# Sheet07.net
KiCad netlist of a schematic drawn in Altium Designer
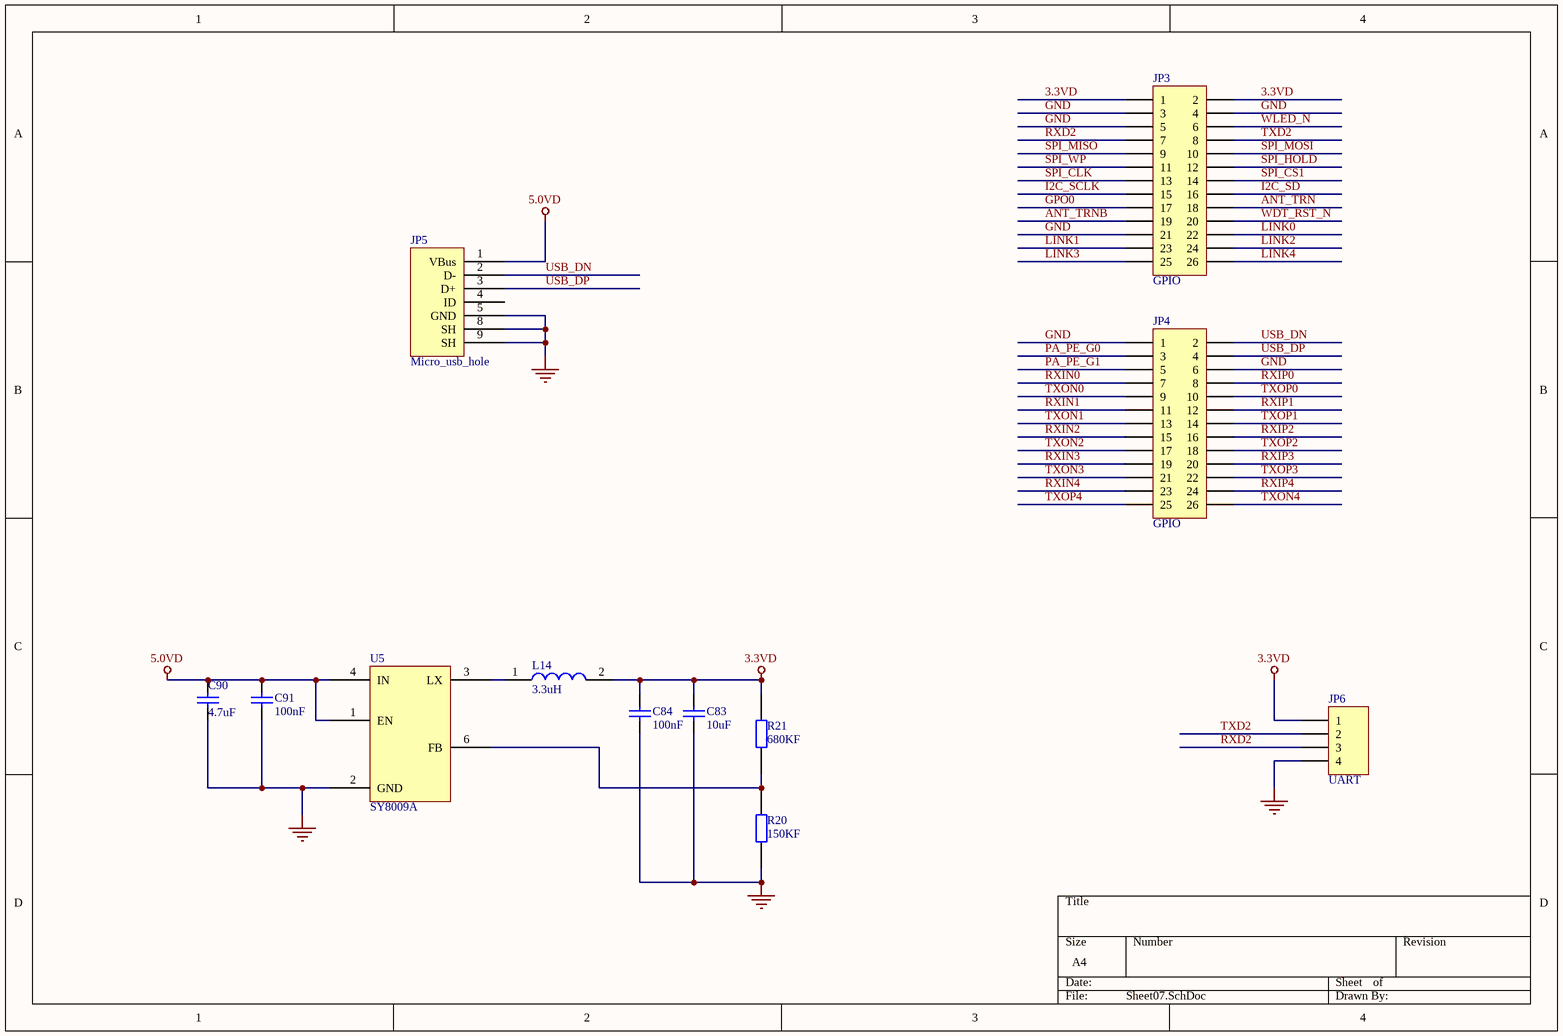
[diagram p0: Sheet07.SchDoc]

(export (version "E")
  (design (tool "Eeschema 10.0.6"))
  (components
    (comp (ref "C83")
      (value "10uF")
      (footprint "R0805")
      (description "2pF, 50V, +/-0.25pF")
      (fields
        (field (name "MANUFACTURER") "Generic Components")
        (field (name "PUBLISHER") "Altium Hobart Technology Centre")
      )
      (libsource (lib "myschlib") (part "Cap Semi"))
    )
    (comp (ref "C84")
      (value "100nF")
      (footprint "R0402")
      (description "2pF, 50V, +/-0.25pF")
      (fields
        (field (name "MANUFACTURER") "Generic Components")
        (field (name "PUBLISHER") "Altium Hobart Technology Centre")
      )
      (libsource (lib "myschlib") (part "Cap Semi"))
    )
    (comp (ref "C90")
      (value "4.7uF")
      (footprint "R0603")
      (description "2pF, 50V, +/-0.25pF")
      (fields
        (field (name "MANUFACTURER") "Generic Components")
        (field (name "PUBLISHER") "Altium Hobart Technology Centre")
      )
      (libsource (lib "myschlib") (part "Cap Semi"))
    )
    (comp (ref "C91")
      (value "100nF")
      (footprint "R0402")
      (description "2pF, 50V, +/-0.25pF")
      (fields
        (field (name "MANUFACTURER") "Generic Components")
        (field (name "PUBLISHER") "Altium Hobart Technology Centre")
      )
      (libsource (lib "myschlib") (part "Cap Semi"))
    )
    (comp (ref "JP3")
      (value "GPIO")
      (footprint "HDR2X13")
      (description "Header, 13-Pin, Dual row")
      (fields (field (name "PUBLISHER") "Altium Limited"))
      (libsource (lib "Miscellaneous Connectors") (part "Header 13X2"))
    )
    (comp (ref "JP4")
      (value "GPIO")
      (footprint "HDR2X13")
      (description "Header, 13-Pin, Dual row")
      (fields (field (name "PUBLISHER") "Altium Limited"))
      (libsource (lib "Miscellaneous Connectors") (part "Header 13X2"))
    )
    (comp (ref "JP5")
      (value "Micro_usb_hole")
      (footprint "Miro_usb_hole")
      (libsource (lib "myschlib") (part "micri_usb_hole"))
    )
    (comp (ref "JP6")
      (value "UART")
      (footprint "HDR1X4")
      (description "Header, 4-Pin")
      (fields (field (name "PUBLISHER") "Altium Limited"))
      (libsource (lib "Miscellaneous Connectors") (part "Header 4"))
    )
    (comp (ref "L14")
      (value "3.3uH")
      (footprint "LSMD3_8x3_8")
      (libsource (lib "myschlib") (part "INDUCTOR"))
    )
    (comp (ref "R20") (value "150KF") (footprint "R0402") (libsource (lib "myschlib") (part "RES")))
    (comp (ref "R21") (value "680KF") (footprint "R0402") (libsource (lib "myschlib") (part "RES")))
    (comp (ref "U5") (value "SY8009A") (footprint "SOT23-6L") (libsource (lib "myschlib") (part "SY8008C")))
  )
  (nets
    (net (code "1") (name "/ANT_TRN") (class "Default")
      (node (ref "JP3") (pin "18") (pinfunction "18_18") (pintype "passive"))
    )
    (net (code "2") (name "/ANT_TRNB") (class "Default")
      (node (ref "JP3") (pin "19") (pinfunction "19_19") (pintype "passive"))
    )
    (net (code "3") (name "/GPO0") (class "Default")
      (node (ref "JP3") (pin "17") (pinfunction "17_17") (pintype "passive"))
    )
    (net (code "4") (name "/I2C_SCLK") (class "Default")
      (node (ref "JP3") (pin "15") (pinfunction "15_15") (pintype "passive"))
    )
    (net (code "5") (name "/I2C_SD") (class "Default")
      (node (ref "JP3") (pin "16") (pinfunction "16_16") (pintype "passive"))
    )
    (net (code "6") (name "/LINK0") (class "Default")
      (node (ref "JP3") (pin "22") (pinfunction "22_22") (pintype "passive"))
    )
    (net (code "7") (name "/LINK1") (class "Default")
      (node (ref "JP3") (pin "23") (pinfunction "23_23") (pintype "passive"))
    )
    (net (code "8") (name "/LINK2") (class "Default")
      (node (ref "JP3") (pin "24") (pinfunction "24_24") (pintype "passive"))
    )
    (net (code "9") (name "/LINK3") (class "Default")
      (node (ref "JP3") (pin "25") (pinfunction "25_25") (pintype "passive"))
    )
    (net (code "10") (name "/LINK4") (class "Default")
      (node (ref "JP3") (pin "26") (pinfunction "26_26") (pintype "passive"))
    )
    (net (code "11") (name "/PA_PE_G0") (class "Default")
      (node (ref "JP4") (pin "3") (pinfunction "3_3") (pintype "passive"))
    )
    (net (code "12") (name "/PA_PE_G1") (class "Default")
      (node (ref "JP4") (pin "5") (pinfunction "5_5") (pintype "passive"))
    )
    (net (code "13") (name "/RXD2") (class "Default")
      (node (ref "JP3") (pin "7") (pinfunction "7_7") (pintype "passive"))
      (node (ref "JP6") (pin "3") (pinfunction "3_3") (pintype "passive"))
    )
    (net (code "14") (name "/RXIN0") (class "Default")
      (node (ref "JP4") (pin "7") (pinfunction "7_7") (pintype "passive"))
    )
    (net (code "15") (name "/RXIN1") (class "Default")
      (node (ref "JP4") (pin "11") (pinfunction "11_11") (pintype "passive"))
    )
    (net (code "16") (name "/RXIN2") (class "Default")
      (node (ref "JP4") (pin "15") (pinfunction "15_15") (pintype "passive"))
    )
    (net (code "17") (name "/RXIN3") (class "Default")
      (node (ref "JP4") (pin "19") (pinfunction "19_19") (pintype "passive"))
    )
    (net (code "18") (name "/RXIN4") (class "Default")
      (node (ref "JP4") (pin "23") (pinfunction "23_23") (pintype "passive"))
    )
    (net (code "19") (name "/RXIP0") (class "Default")
      (node (ref "JP4") (pin "8") (pinfunction "8_8") (pintype "passive"))
    )
    (net (code "20") (name "/RXIP1") (class "Default")
      (node (ref "JP4") (pin "12") (pinfunction "12_12") (pintype "passive"))
    )
    (net (code "21") (name "/RXIP2") (class "Default")
      (node (ref "JP4") (pin "16") (pinfunction "16_16") (pintype "passive"))
    )
    (net (code "22") (name "/RXIP3") (class "Default")
      (node (ref "JP4") (pin "20") (pinfunction "20_20") (pintype "passive"))
    )
    (net (code "23") (name "/RXIP4") (class "Default")
      (node (ref "JP4") (pin "24") (pinfunction "24_24") (pintype "passive"))
    )
    (net (code "24") (name "/SPI_CLK") (class "Default")
      (node (ref "JP3") (pin "13") (pinfunction "13_13") (pintype "passive"))
    )
    (net (code "25") (name "/SPI_CS1") (class "Default")
      (node (ref "JP3") (pin "14") (pinfunction "14_14") (pintype "passive"))
    )
    (net (code "26") (name "/SPI_HOLD") (class "Default")
      (node (ref "JP3") (pin "12") (pinfunction "12_12") (pintype "passive"))
    )
    (net (code "27") (name "/SPI_MISO") (class "Default")
      (node (ref "JP3") (pin "9") (pinfunction "9_9") (pintype "passive"))
    )
    (net (code "28") (name "/SPI_MOSI") (class "Default")
      (node (ref "JP3") (pin "10") (pinfunction "10_10") (pintype "passive"))
    )
    (net (code "29") (name "/SPI_WP") (class "Default")
      (node (ref "JP3") (pin "11") (pinfunction "11_11") (pintype "passive"))
    )
    (net (code "30") (name "/TXD2") (class "Default")
      (node (ref "JP3") (pin "8") (pinfunction "8_8") (pintype "passive"))
      (node (ref "JP6") (pin "2") (pinfunction "2_2") (pintype "passive"))
    )
    (net (code "31") (name "/TXON0") (class "Default")
      (node (ref "JP4") (pin "9") (pinfunction "9_9") (pintype "passive"))
    )
    (net (code "32") (name "/TXON1") (class "Default")
      (node (ref "JP4") (pin "13") (pinfunction "13_13") (pintype "passive"))
    )
    (net (code "33") (name "/TXON2") (class "Default")
      (node (ref "JP4") (pin "17") (pinfunction "17_17") (pintype "passive"))
    )
    (net (code "34") (name "/TXON3") (class "Default")
      (node (ref "JP4") (pin "21") (pinfunction "21_21") (pintype "passive"))
    )
    (net (code "35") (name "/TXON4") (class "Default")
      (node (ref "JP4") (pin "26") (pinfunction "26_26") (pintype "passive"))
    )
    (net (code "36") (name "/TXOP0") (class "Default")
      (node (ref "JP4") (pin "10") (pinfunction "10_10") (pintype "passive"))
    )
    (net (code "37") (name "/TXOP1") (class "Default")
      (node (ref "JP4") (pin "14") (pinfunction "14_14") (pintype "passive"))
    )
    (net (code "38") (name "/TXOP2") (class "Default")
      (node (ref "JP4") (pin "18") (pinfunction "18_18") (pintype "passive"))
    )
    (net (code "39") (name "/TXOP3") (class "Default")
      (node (ref "JP4") (pin "22") (pinfunction "22_22") (pintype "passive"))
    )
    (net (code "40") (name "/TXOP4") (class "Default")
      (node (ref "JP4") (pin "25") (pinfunction "25_25") (pintype "passive"))
    )
    (net (code "41") (name "/USB_DN") (class "Default")
      (node (ref "JP4") (pin "2") (pinfunction "2_2") (pintype "passive"))
      (node (ref "JP5") (pin "2") (pinfunction "D-_2") (pintype "passive"))
    )
    (net (code "42") (name "/USB_DP") (class "Default")
      (node (ref "JP4") (pin "4") (pinfunction "4_4") (pintype "passive"))
      (node (ref "JP5") (pin "3") (pinfunction "D+_3") (pintype "passive"))
    )
    (net (code "43") (name "/WDT_RST_N") (class "Default")
      (node (ref "JP3") (pin "20") (pinfunction "20_20") (pintype "passive"))
    )
    (net (code "44") (name "/WLED_N") (class "Default")
      (node (ref "JP3") (pin "6") (pinfunction "6_6") (pintype "passive"))
    )
    (net (code "45") (name "3.3VD") (class "Default")
      (node (ref "C83") (pin "1") (pinfunction "1_1") (pintype "passive"))
      (node (ref "C84") (pin "1") (pinfunction "1_1") (pintype "passive"))
      (node (ref "JP3") (pin "1") (pinfunction "1_1") (pintype "passive"))
      (node (ref "JP3") (pin "2") (pinfunction "2_2") (pintype "passive"))
      (node (ref "JP6") (pin "1") (pinfunction "1_1") (pintype "passive"))
      (node (ref "L14") (pin "2") (pinfunction "2_2") (pintype "passive"))
      (node (ref "R21") (pin "1") (pinfunction "1_1") (pintype "passive"))
    )
    (net (code "46") (name "5.0VD") (class "Default")
      (node (ref "C90") (pin "2") (pinfunction "2_2") (pintype "passive"))
      (node (ref "C91") (pin "1") (pinfunction "1_1") (pintype "passive"))
      (node (ref "JP5") (pin "1") (pinfunction "VBus_1") (pintype "power_in"))
      (node (ref "U5") (pin "1") (pinfunction "EN_1") (pintype "passive"))
      (node (ref "U5") (pin "4") (pinfunction "IN_4") (pintype "passive"))
    )
    (net (code "47") (name "GND") (class "Default")
      (node (ref "C83") (pin "2") (pinfunction "2_2") (pintype "passive"))
      (node (ref "C84") (pin "2") (pinfunction "2_2") (pintype "passive"))
      (node (ref "C90") (pin "1") (pinfunction "1_1") (pintype "passive"))
      (node (ref "C91") (pin "2") (pinfunction "2_2") (pintype "passive"))
      (node (ref "JP3") (pin "21") (pinfunction "21_21") (pintype "passive"))
      (node (ref "JP3") (pin "3") (pinfunction "3_3") (pintype "passive"))
      (node (ref "JP3") (pin "4") (pinfunction "4_4") (pintype "passive"))
      (node (ref "JP3") (pin "5") (pinfunction "5_5") (pintype "passive"))
      (node (ref "JP4") (pin "1") (pinfunction "1_1") (pintype "passive"))
      (node (ref "JP4") (pin "6") (pinfunction "6_6") (pintype "passive"))
      (node (ref "JP5") (pin "5") (pinfunction "GND_5") (pintype "passive"))
      (node (ref "JP5") (pin "8") (pinfunction "SH_8") (pintype "passive"))
      (node (ref "JP5") (pin "9") (pinfunction "SH_9") (pintype "passive"))
      (node (ref "JP6") (pin "4") (pinfunction "4_4") (pintype "passive"))
      (node (ref "R20") (pin "2") (pinfunction "2_2") (pintype "passive"))
      (node (ref "U5") (pin "2") (pinfunction "GND_2") (pintype "passive"))
    )
    (net (code "48") (name "Net-(U5-FB)") (class "Default")
      (node (ref "R20") (pin "1") (pinfunction "1_1") (pintype "passive"))
      (node (ref "R21") (pin "2") (pinfunction "2_2") (pintype "passive"))
      (node (ref "U5") (pin "6") (pinfunction "FB_6") (pintype "passive"))
    )
    (net (code "49") (name "Net-(U5-LX)") (class "Default")
      (node (ref "L14") (pin "1") (pinfunction "1_1") (pintype "passive"))
      (node (ref "U5") (pin "3") (pinfunction "LX_3") (pintype "passive"))
    )
    (net (code "50") (name "unconnected-(JP5-ID-Pad4)") (class "Default")
      (node (ref "JP5") (pin "4") (pinfunction "ID_4") (pintype "passive"))
    )
  )
)
